# SinWaveCreator.net
KiCad netlist of a schematic drawn in Altium Designer
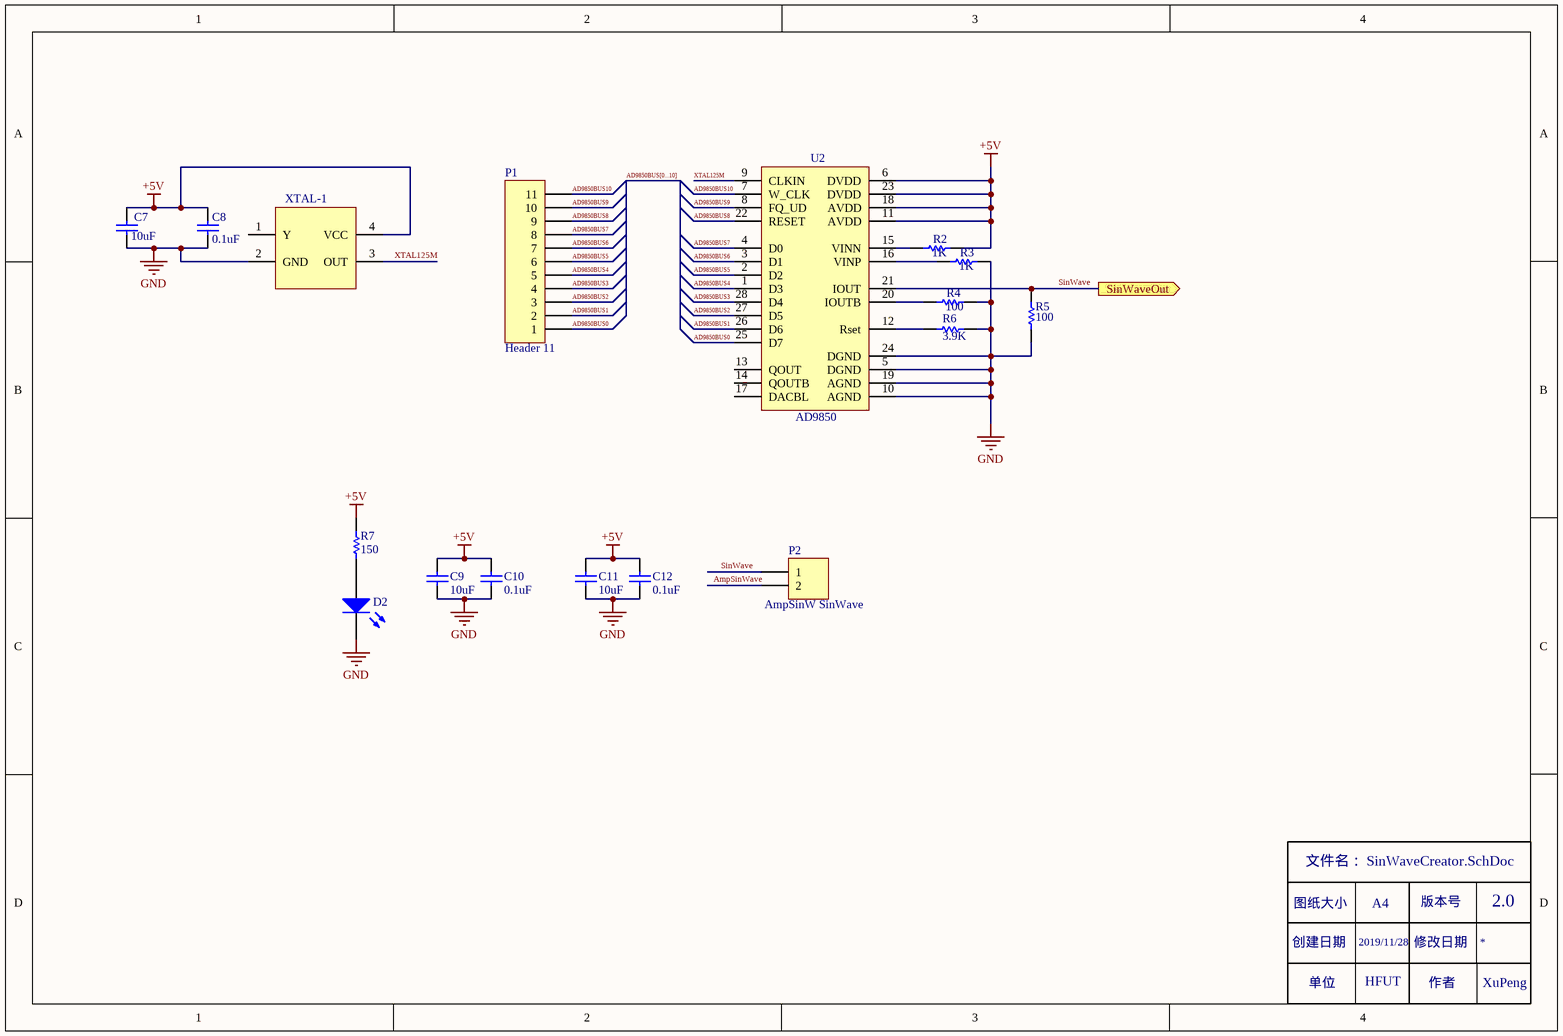
[diagram p0: SinWaveCreator.SchDoc]

(export (version "E")
  (design (tool "Eeschema 10.0.6"))
  (components
    (comp (ref "C7")
      (value "10uF")
      (footprint "RB0.1/0.2")
      (description "无极性电容")
      (fields (field (name "Comment") "Cap") (field (name "PUBLISHER") "Altium Limited"))
      (libsource (lib "Fszhang") (part "Cap"))
    )
    (comp (ref "C8")
      (value "0.1uF")
      (footprint "C-RAD")
      (description "无极性电容")
      (fields (field (name "Comment") "Cap") (field (name "PUBLISHER") "Altium Limited"))
      (libsource (lib "Fszhang") (part "Cap"))
    )
    (comp (ref "C9")
      (value "10uF")
      (footprint "RB0.1/0.2")
      (description "无极性电容")
      (fields (field (name "Comment") "Cap") (field (name "PUBLISHER") "Altium Limited"))
      (libsource (lib "Fszhang") (part "Cap"))
    )
    (comp (ref "C10")
      (value "0.1uF")
      (footprint "C-RAD")
      (description "无极性电容")
      (fields (field (name "Comment") "Cap") (field (name "PUBLISHER") "Altium Limited"))
      (libsource (lib "Fszhang") (part "Cap"))
    )
    (comp (ref "C11")
      (value "10uF")
      (footprint "RB0.1/0.2")
      (description "无极性电容")
      (fields (field (name "Comment") "Cap") (field (name "PUBLISHER") "Altium Limited"))
      (libsource (lib "Fszhang") (part "Cap"))
    )
    (comp (ref "C12")
      (value "0.1uF")
      (footprint "C-RAD")
      (description "无极性电容")
      (fields (field (name "Comment") "Cap") (field (name "PUBLISHER") "Altium Limited"))
      (libsource (lib "Fszhang") (part "Cap"))
    )
    (comp (ref "D2")
      (value "LED0")
      (footprint "RB2.54/4")
      (description "Typical INFRARED GaAs LED")
      (fields (field (name "PUBLISHER") "Altium Limited"))
      (libsource (lib "Miscellaneous Devices") (part "LED0"))
    )
    (comp (ref "P1")
      (value "Header 11")
      (footprint "HDR1X11")
      (description "Header, 11-Pin")
      (fields (field (name "PUBLISHER") "Altium Limited"))
      (libsource (lib "Miscellaneous Connectors") (part "Header 11"))
    )
    (comp (ref "P2")
      (value "AmpSinW SinWave")
      (footprint "HDR1X2")
      (description "Header, 2-Pin")
      (fields (field (name "PUBLISHER") "Altium Limited"))
      (libsource (lib "Miscellaneous Connectors") (part "Header 2"))
    )
    (comp (ref "R2")
      (value "1K")
      (footprint "AXIAL-0.3")
      (description "Resistor")
      (fields (field (name "Comment") "Res1") (field (name "PUBLISHER") "Altium Limited"))
      (libsource (lib "Miscellaneous Devices") (part "Res1"))
    )
    (comp (ref "R3")
      (value "1K")
      (footprint "AXIAL-0.3")
      (description "Resistor")
      (fields (field (name "Comment") "Res1") (field (name "PUBLISHER") "Altium Limited"))
      (libsource (lib "Miscellaneous Devices") (part "Res1"))
    )
    (comp (ref "R4")
      (value "100")
      (footprint "AXIAL-0.3")
      (description "Resistor")
      (fields (field (name "Comment") "Res1") (field (name "PUBLISHER") "Altium Limited"))
      (libsource (lib "Miscellaneous Devices") (part "Res1"))
    )
    (comp (ref "R5")
      (value "100")
      (footprint "AXIAL-0.3")
      (description "Resistor")
      (fields (field (name "Comment") "Res1") (field (name "PUBLISHER") "Altium Limited"))
      (libsource (lib "Miscellaneous Devices") (part "Res1"))
    )
    (comp (ref "R6")
      (value "3.9K")
      (footprint "AXIAL-0.3")
      (description "Resistor")
      (fields (field (name "Comment") "Res1") (field (name "PUBLISHER") "Altium Limited"))
      (libsource (lib "Miscellaneous Devices") (part "Res1"))
    )
    (comp (ref "R7")
      (value "150")
      (footprint "AXIAL-0.3")
      (description "Resistor")
      (fields (field (name "Comment") "Res1") (field (name "PUBLISHER") "Altium Limited"))
      (libsource (lib "Miscellaneous Devices") (part "Res1"))
    )
    (comp (ref "U2")
      (value "AD9850")
      (footprint "SSOP28")
      (libsource (lib "ElectricalConductivityMeterIntLib") (part "AD9850"))
    )
    (comp (ref "XTAL-1")
      (value "XTAL-125M-7.62")
      (footprint "XTAL-4-7.62")
      (libsource (lib "ElectricalConductivityMeterIntLib-20.5.9") (part "XTAL-125M-7.62"))
    )
  )
  (nets
    (net (code "2") (name "+5V") (class "Default")
      (node (ref "C10") (pin "2") (pinfunction "2_2") (pintype "passive"))
      (node (ref "C11") (pin "2") (pinfunction "2_2") (pintype "passive"))
      (node (ref "C12") (pin "2") (pinfunction "2_2") (pintype "passive"))
      (node (ref "C7") (pin "2") (pinfunction "2_2") (pintype "passive"))
      (node (ref "C8") (pin "2") (pinfunction "2_2") (pintype "passive"))
      (node (ref "C9") (pin "2") (pinfunction "2_2") (pintype "passive"))
      (node (ref "R2") (pin "2") (pinfunction "2_2") (pintype "passive"))
      (node (ref "R7") (pin "2") (pinfunction "2_2") (pintype "passive"))
      (node (ref "U2") (pin "11") (pinfunction "AVDD_11") (pintype "passive"))
      (node (ref "U2") (pin "18") (pinfunction "AVDD_18") (pintype "passive"))
      (node (ref "U2") (pin "23") (pinfunction "DVDD_23") (pintype "passive"))
      (node (ref "U2") (pin "6") (pinfunction "DVDD_6") (pintype "passive"))
      (node (ref "XTAL-1") (pin "4") (pinfunction "VCC_4") (pintype "passive"))
    )
    (net (code "3") (name "/AD9850BUS0") (class "Default")
      (node (ref "P1") (pin "1") (pinfunction "1_1") (pintype "passive"))
      (node (ref "U2") (pin "25") (pinfunction "D7_25") (pintype "passive"))
    )
    (net (code "4") (name "/AD9850BUS1") (class "Default")
      (node (ref "P1") (pin "2") (pinfunction "2_2") (pintype "passive"))
      (node (ref "U2") (pin "26") (pinfunction "D6_26") (pintype "passive"))
    )
    (net (code "5") (name "/AD9850BUS2") (class "Default")
      (node (ref "P1") (pin "3") (pinfunction "3_3") (pintype "passive"))
      (node (ref "U2") (pin "27") (pinfunction "D5_27") (pintype "passive"))
    )
    (net (code "6") (name "/AD9850BUS3") (class "Default")
      (node (ref "P1") (pin "4") (pinfunction "4_4") (pintype "passive"))
      (node (ref "U2") (pin "28") (pinfunction "D4_28") (pintype "passive"))
    )
    (net (code "7") (name "/AD9850BUS4") (class "Default")
      (node (ref "P1") (pin "5") (pinfunction "5_5") (pintype "passive"))
      (node (ref "U2") (pin "1") (pinfunction "D3_1") (pintype "passive"))
    )
    (net (code "8") (name "/AD9850BUS5") (class "Default")
      (node (ref "P1") (pin "6") (pinfunction "6_6") (pintype "passive"))
      (node (ref "U2") (pin "2") (pinfunction "D2_2") (pintype "passive"))
    )
    (net (code "9") (name "/AD9850BUS6") (class "Default")
      (node (ref "P1") (pin "7") (pinfunction "7_7") (pintype "passive"))
      (node (ref "U2") (pin "3") (pinfunction "D1_3") (pintype "passive"))
    )
    (net (code "10") (name "/AD9850BUS7") (class "Default")
      (node (ref "P1") (pin "8") (pinfunction "8_8") (pintype "passive"))
      (node (ref "U2") (pin "4") (pinfunction "D0_4") (pintype "passive"))
    )
    (net (code "11") (name "/AD9850BUS8") (class "Default")
      (node (ref "P1") (pin "9") (pinfunction "9_9") (pintype "passive"))
      (node (ref "U2") (pin "22") (pinfunction "RESET_22") (pintype "passive"))
    )
    (net (code "12") (name "/AD9850BUS9") (class "Default")
      (node (ref "P1") (pin "10") (pinfunction "10_10") (pintype "passive"))
      (node (ref "U2") (pin "8") (pinfunction "FQ_UD_8") (pintype "passive"))
    )
    (net (code "13") (name "/AD9850BUS10") (class "Default")
      (node (ref "P1") (pin "11") (pinfunction "11_11") (pintype "passive"))
      (node (ref "U2") (pin "7") (pinfunction "W_CLK_7") (pintype "passive"))
    )
    (net (code "14") (name "/AmpSinWave") (class "Default")
      (node (ref "P2") (pin "2") (pinfunction "2_2") (pintype "passive"))
    )
    (net (code "15") (name "/SinWave") (class "Default")
      (node (ref "P2") (pin "1") (pinfunction "1_1") (pintype "passive"))
      (node (ref "R5") (pin "2") (pinfunction "2_2") (pintype "passive"))
      (node (ref "U2") (pin "21") (pinfunction "IOUT_21") (pintype "passive"))
    )
    (net (code "16") (name "/XTAL125M") (class "Default")
      (node (ref "U2") (pin "9") (pinfunction "CLKIN_9") (pintype "passive"))
      (node (ref "XTAL-1") (pin "3") (pinfunction "OUT_3") (pintype "passive"))
    )
    (net (code "18") (name "GND") (class "Default")
      (node (ref "C10") (pin "1") (pinfunction "1_1") (pintype "passive"))
      (node (ref "C11") (pin "1") (pinfunction "1_1") (pintype "passive"))
      (node (ref "C12") (pin "1") (pinfunction "1_1") (pintype "passive"))
      (node (ref "C7") (pin "1") (pinfunction "1_1") (pintype "passive"))
      (node (ref "C8") (pin "1") (pinfunction "1_1") (pintype "passive"))
      (node (ref "C9") (pin "1") (pinfunction "1_1") (pintype "passive"))
      (node (ref "D2") (pin "2") (pinfunction "K_2") (pintype "passive"))
      (node (ref "R3") (pin "2") (pinfunction "2_2") (pintype "passive"))
      (node (ref "R4") (pin "2") (pinfunction "2_2") (pintype "passive"))
      (node (ref "R5") (pin "1") (pinfunction "1_1") (pintype "passive"))
      (node (ref "R6") (pin "2") (pinfunction "2_2") (pintype "passive"))
      (node (ref "U2") (pin "10") (pinfunction "AGND_10") (pintype "passive"))
      (node (ref "U2") (pin "19") (pinfunction "AGND_19") (pintype "passive"))
      (node (ref "U2") (pin "24") (pinfunction "DGND_24") (pintype "passive"))
      (node (ref "U2") (pin "5") (pinfunction "DGND_5") (pintype "passive"))
      (node (ref "XTAL-1") (pin "2") (pinfunction "GND_2") (pintype "passive"))
    )
    (net (code "19") (name "Net-(D2-A)") (class "Default")
      (node (ref "D2") (pin "1") (pinfunction "A_1") (pintype "passive"))
      (node (ref "R7") (pin "1") (pinfunction "1_1") (pintype "passive"))
    )
    (net (code "20") (name "Net-(U2-IOUTB)") (class "Default")
      (node (ref "R4") (pin "1") (pinfunction "1_1") (pintype "passive"))
      (node (ref "U2") (pin "20") (pinfunction "IOUTB_20") (pintype "passive"))
    )
    (net (code "21") (name "Net-(U2-Rset)") (class "Default")
      (node (ref "R6") (pin "1") (pinfunction "1_1") (pintype "passive"))
      (node (ref "U2") (pin "12") (pinfunction "Rset_12") (pintype "passive"))
    )
    (net (code "22") (name "Net-(U2-VINN)") (class "Default")
      (node (ref "R2") (pin "1") (pinfunction "1_1") (pintype "passive"))
      (node (ref "U2") (pin "15") (pinfunction "VINN_15") (pintype "passive"))
    )
    (net (code "23") (name "Net-(U2-VINP)") (class "Default")
      (node (ref "R3") (pin "1") (pinfunction "1_1") (pintype "passive"))
      (node (ref "U2") (pin "16") (pinfunction "VINP_16") (pintype "passive"))
    )
    (net (code "24") (name "unconnected-(U2-DACBL-Pad17)") (class "Default")
      (node (ref "U2") (pin "17") (pinfunction "DACBL_17") (pintype "passive"))
    )
    (net (code "25") (name "unconnected-(U2-QOUT-Pad13)") (class "Default")
      (node (ref "U2") (pin "13") (pinfunction "QOUT_13") (pintype "passive"))
    )
    (net (code "26") (name "unconnected-(U2-QOUTB-Pad14)") (class "Default")
      (node (ref "U2") (pin "14") (pinfunction "QOUTB_14") (pintype "passive"))
    )
    (net (code "27") (name "unconnected-(XTAL-1-Y-Pad1)") (class "Default")
      (node (ref "XTAL-1") (pin "1") (pinfunction "Y_1") (pintype "passive"))
    )
  )
)
